# TAC_v1.net
KiCad netlist of a schematic drawn in Altium Designer
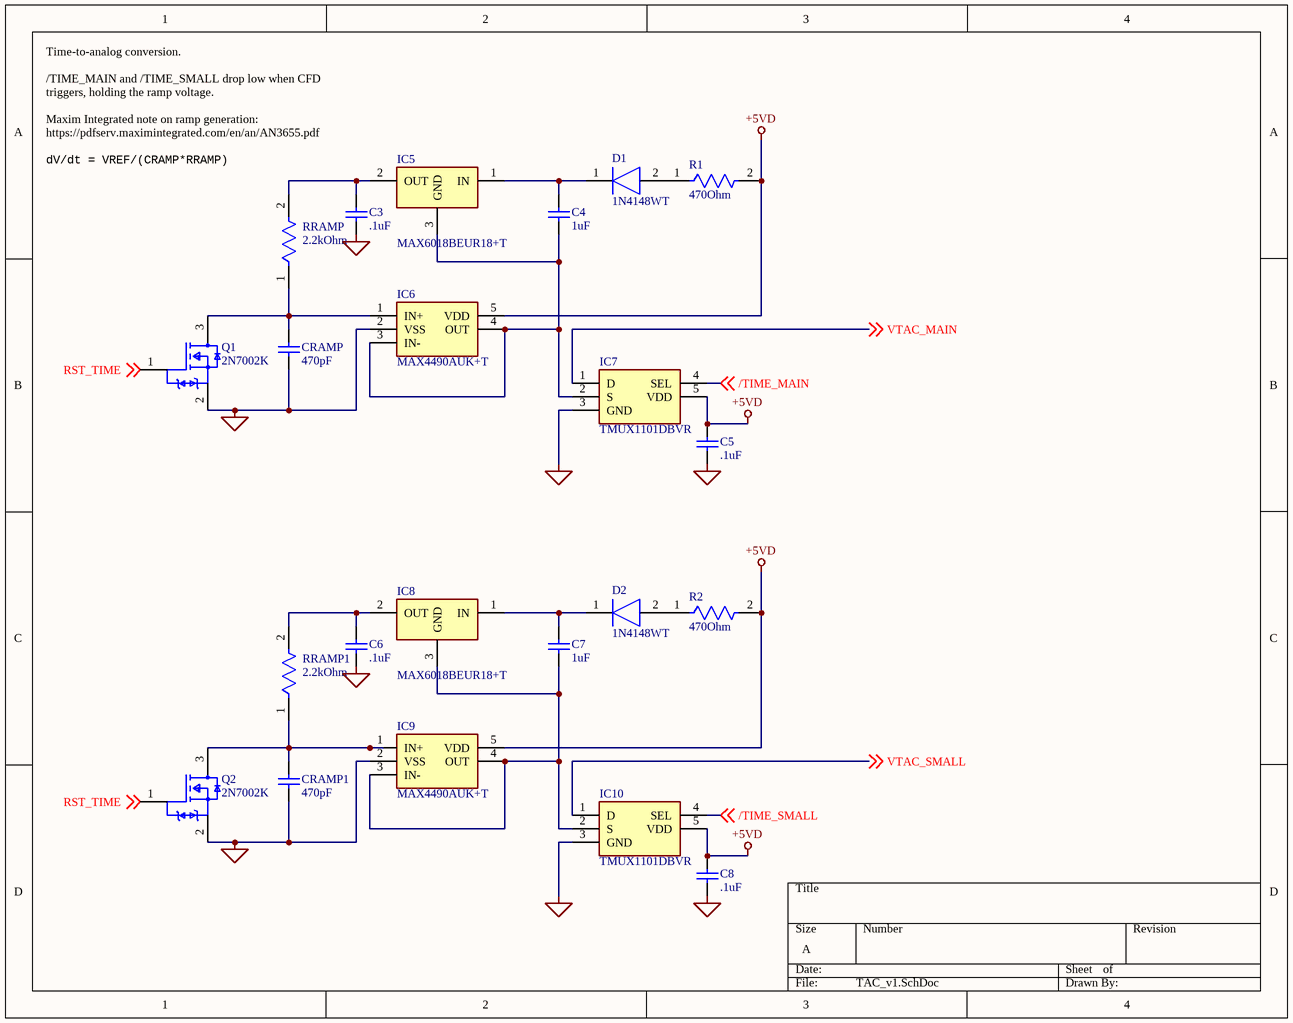
[diagram p0: TAC_v1.SchDoc]

(export (version "E")
  (design (tool "Eeschema 10.0.6"))
  (components
    (comp (ref "C3")
      (value ".1uF")
      (footprint "CAPC2013X140X45NL15T25")
      (description "0402")
      (fields (field (name "PART NUMBER") "GRM21BR71A106KE51L") (field (name "MANUFACTURER") "Murata"))
      (libsource (lib "Altium Content Vault") (part "CAP"))
    )
    (comp (ref "C4")
      (value "1uF")
      (footprint "CAPC2013X140X45NL15T25")
      (description "0402")
      (fields (field (name "PART NUMBER") "GRM21BR71A106KE51L") (field (name "MANUFACTURER") "Murata"))
      (libsource (lib "Altium Content Vault") (part "CAP"))
    )
    (comp (ref "C5")
      (value ".1uF")
      (footprint "CAPC2013X140X45NL15T25")
      (description "0402")
      (fields (field (name "PART NUMBER") "GRM21BR71A106KE51L") (field (name "MANUFACTURER") "Murata"))
      (libsource (lib "Altium Content Vault") (part "CAP"))
    )
    (comp (ref "C6")
      (value ".1uF")
      (footprint "CAPC2013X140X45NL15T25")
      (description "0402")
      (fields (field (name "PART NUMBER") "GRM21BR71A106KE51L") (field (name "MANUFACTURER") "Murata"))
      (libsource (lib "Altium Content Vault") (part "CAP"))
    )
    (comp (ref "C7")
      (value "1uF")
      (footprint "CAPC2013X140X45NL15T25")
      (description "0402")
      (fields (field (name "PART NUMBER") "GRM21BR71A106KE51L") (field (name "MANUFACTURER") "Murata"))
      (libsource (lib "Altium Content Vault") (part "CAP"))
    )
    (comp (ref "C8")
      (value ".1uF")
      (footprint "CAPC2013X140X45NL15T25")
      (description "0402")
      (fields (field (name "PART NUMBER") "GRM21BR71A106KE51L") (field (name "MANUFACTURER") "Murata"))
      (libsource (lib "Altium Content Vault") (part "CAP"))
    )
    (comp (ref "CRAMP")
      (value "470pF")
      (footprint "CAPC2013X140X45NL15T25")
      (description "0402")
      (fields (field (name "PART NUMBER") "GRM21BR71A106KE51L") (field (name "MANUFACTURER") "Murata"))
      (libsource (lib "Altium Content Vault") (part "CAP"))
    )
    (comp (ref "CRAMP1")
      (value "470pF")
      (footprint "CAPC2013X140X45NL15T25")
      (description "0402")
      (fields (field (name "PART NUMBER") "GRM21BR71A106KE51L") (field (name "MANUFACTURER") "Murata"))
      (libsource (lib "Altium Content Vault") (part "CAP"))
    )
    (comp (ref "D1")
      (value "1N4148WT")
      (footprint "SamacSys:SODFL1608X70N")
      (description "Diode")
      (libsource (lib "*") (part "1N4148WT"))
    )
    (comp (ref "D2")
      (value "1N4148WT")
      (footprint "SamacSys:SODFL1608X70N")
      (description "Diode")
      (libsource (lib "*") (part "1N4148WT"))
    )
    (comp (ref "IC5")
      (value "MAX6018BEUR18+T")
      (footprint "SamacSys:SOT95P237X112-3N")
      (description "Voltage References Precision, Micropower, 1.8V Supply, Low-Dropout, SOT23 Voltage Reference")
      (libsource (lib "SamacSys") (part "MAX6018BEUR18+T"))
    )
    (comp (ref "IC6")
      (value "MAX4490AUK+T")
      (footprint "SamacSys:SOT95P280X145-5N")
      (description "Integrated Circuit")
      (libsource (lib "SamacSys") (part "MAX4490AUK+T"))
    )
    (comp (ref "IC7")
      (value "TMUX1101DBVR")
      (footprint "SamacSys:SOT95P280X145-5N")
      (libsource (lib "*") (part "TMUX1101DBVR"))
    )
    (comp (ref "IC8")
      (value "MAX6018BEUR18+T")
      (footprint "SamacSys:SOT95P237X112-3N")
      (description "Voltage References Precision, Micropower, 1.8V Supply, Low-Dropout, SOT23 Voltage Reference")
      (libsource (lib "SamacSys") (part "MAX6018BEUR18+T"))
    )
    (comp (ref "IC9")
      (value "MAX4490AUK+T")
      (footprint "SamacSys:SOT95P280X145-5N")
      (description "Integrated Circuit")
      (libsource (lib "SamacSys") (part "MAX4490AUK+T"))
    )
    (comp (ref "IC10")
      (value "TMUX1101DBVR")
      (footprint "SamacSys:SOT95P280X145-5N")
      (libsource (lib "*") (part "TMUX1101DBVR"))
    )
    (comp (ref "Q1")
      (value "2N7002K")
      (footprint "FP-318-08-MFG")
      (description "MOSFET N-CH 60V 300MA SOT23")
      (fields
        (field (name "OCTOPART") "https://octopart.com/2n7002k-on+semiconductor-84408900")
        (field (name "MANUFACTURER") "ON Semiconductor")
      )
      (libsource (lib "Altium Content Vault") (part "40bafa8609a25cdbb0dab398ef4a0d9"))
    )
    (comp (ref "Q2")
      (value "2N7002K")
      (footprint "FP-318-08-MFG")
      (description "MOSFET N-CH 60V 300MA SOT23")
      (fields
        (field (name "OCTOPART") "https://octopart.com/2n7002k-on+semiconductor-84408900")
        (field (name "MANUFACTURER") "ON Semiconductor")
      )
      (libsource (lib "Altium Content Vault") (part "40bafa8609a25cdbb0dab398ef4a0d9"))
    )
    (comp (ref "R1")
      (value "470Ohm")
      (footprint "FP-CRCW0402-e3-IPC_C")
      (description "RES Thick Film, 0Ω, 0.063W, 0402")
      (fields (field (name "TOLERANCE") "5%"))
      (libsource (lib "Altium Content Vault") (part "1029c3af85768c4190bb7ad29bc67b5"))
    )
    (comp (ref "R2")
      (value "470Ohm")
      (footprint "FP-CRCW0402-e3-IPC_C")
      (description "RES Thick Film, 0Ω, 0.063W, 0402")
      (fields (field (name "TOLERANCE") "5%"))
      (libsource (lib "Altium Content Vault") (part "1029c3af85768c4190bb7ad29bc67b5"))
    )
    (comp (ref "RRAMP")
      (value "2.2kOhm")
      (footprint "FP-CRCW0603-e3-MFG")
      (description "RES Thick Film, 1MΩ, 1%, 0.1W, 100ppm/°C, 0603")
      (fields (field (name "TOLERANCE") "1%"))
      (libsource (lib "Altium Content Vault") (part "1029c3af85768c4190bb7ad29bc67b5"))
    )
    (comp (ref "RRAMP1")
      (value "2.2kOhm")
      (footprint "FP-CRCW0603-e3-MFG")
      (description "RES Thick Film, 1MΩ, 1%, 0.1W, 100ppm/°C, 0603")
      (fields (field (name "TOLERANCE") "1%"))
      (libsource (lib "Altium Content Vault") (part "1029c3af85768c4190bb7ad29bc67b5"))
    )
  )
  (nets
    (net (code "1") (name "+5VD") (class "Default")
      (node (ref "C5") (pin "2") (pinfunction "2_2") (pintype "passive"))
      (node (ref "C8") (pin "2") (pinfunction "2_2") (pintype "passive"))
      (node (ref "IC10") (pin "5") (pinfunction "VDD_5") (pintype "passive"))
      (node (ref "IC6") (pin "5") (pinfunction "VDD_5") (pintype "passive"))
      (node (ref "IC7") (pin "5") (pinfunction "VDD_5") (pintype "passive"))
      (node (ref "IC9") (pin "5") (pinfunction "VDD_5") (pintype "passive"))
      (node (ref "R1") (pin "2") (pinfunction "2_2") (pintype "passive"))
      (node (ref "R2") (pin "2") (pinfunction "2_2") (pintype "passive"))
    )
    (net (code "2") (name "GND") (class "Default")
      (node (ref "C3") (pin "1") (pinfunction "1_1") (pintype "passive"))
      (node (ref "C5") (pin "1") (pinfunction "1_1") (pintype "passive"))
      (node (ref "C6") (pin "1") (pinfunction "1_1") (pintype "passive"))
      (node (ref "C8") (pin "1") (pinfunction "1_1") (pintype "passive"))
      (node (ref "CRAMP") (pin "1") (pinfunction "1_1") (pintype "passive"))
      (node (ref "CRAMP1") (pin "1") (pinfunction "1_1") (pintype "passive"))
      (node (ref "IC10") (pin "3") (pinfunction "GND_3") (pintype "passive"))
      (node (ref "IC6") (pin "2") (pinfunction "VSS_2") (pintype "passive"))
      (node (ref "IC7") (pin "3") (pinfunction "GND_3") (pintype "passive"))
      (node (ref "IC9") (pin "2") (pinfunction "VSS_2") (pintype "passive"))
      (node (ref "Q1") (pin "2") (pinfunction "Source_2") (pintype "passive"))
      (node (ref "Q2") (pin "2") (pinfunction "Source_2") (pintype "passive"))
    )
    (net (code "3") (name "Net-(D1-A)") (class "Default")
      (node (ref "D1") (pin "2") (pinfunction "A_2") (pintype "passive"))
      (node (ref "R1") (pin "1") (pinfunction "1_1") (pintype "passive"))
    )
    (net (code "4") (name "Net-(D1-K)") (class "Default")
      (node (ref "C4") (pin "2") (pinfunction "2_2") (pintype "passive"))
      (node (ref "D1") (pin "1") (pinfunction "K_1") (pintype "passive"))
      (node (ref "IC5") (pin "1") (pinfunction "IN_1") (pintype "passive"))
    )
    (net (code "5") (name "Net-(D2-A)") (class "Default")
      (node (ref "D2") (pin "2") (pinfunction "A_2") (pintype "passive"))
      (node (ref "R2") (pin "1") (pinfunction "1_1") (pintype "passive"))
    )
    (net (code "6") (name "Net-(D2-K)") (class "Default")
      (node (ref "C7") (pin "2") (pinfunction "2_2") (pintype "passive"))
      (node (ref "D2") (pin "1") (pinfunction "K_1") (pintype "passive"))
      (node (ref "IC8") (pin "1") (pinfunction "IN_1") (pintype "passive"))
    )
    (net (code "7") (name "Net-(IC5-GND)") (class "Default")
      (node (ref "C4") (pin "1") (pinfunction "1_1") (pintype "passive"))
      (node (ref "IC5") (pin "3") (pinfunction "GND_3") (pintype "passive"))
      (node (ref "IC6") (pin "3") (pinfunction "IN-_3") (pintype "passive"))
      (node (ref "IC6") (pin "4") (pinfunction "OUT_4") (pintype "passive"))
      (node (ref "IC7") (pin "2") (pinfunction "S_2") (pintype "passive"))
    )
    (net (code "8") (name "Net-(IC5-OUT)") (class "Default")
      (node (ref "C3") (pin "2") (pinfunction "2_2") (pintype "passive"))
      (node (ref "IC5") (pin "2") (pinfunction "OUT_2") (pintype "passive"))
      (node (ref "RRAMP") (pin "2") (pinfunction "2_2") (pintype "passive"))
    )
    (net (code "9") (name "Net-(IC6-IN+)") (class "Default")
      (node (ref "CRAMP") (pin "2") (pinfunction "2_2") (pintype "passive"))
      (node (ref "IC6") (pin "1") (pinfunction "IN+_1") (pintype "passive"))
      (node (ref "Q1") (pin "3") (pinfunction "Drain_3") (pintype "passive"))
      (node (ref "RRAMP") (pin "1") (pinfunction "1_1") (pintype "passive"))
    )
    (net (code "10") (name "Net-(IC8-OUT)") (class "Default")
      (node (ref "C6") (pin "2") (pinfunction "2_2") (pintype "passive"))
      (node (ref "IC8") (pin "2") (pinfunction "OUT_2") (pintype "passive"))
      (node (ref "RRAMP1") (pin "2") (pinfunction "2_2") (pintype "passive"))
    )
    (net (code "11") (name "Net-(IC9-IN+)") (class "Default")
      (node (ref "CRAMP1") (pin "2") (pinfunction "2_2") (pintype "passive"))
      (node (ref "IC9") (pin "1") (pinfunction "IN+_1") (pintype "passive"))
      (node (ref "Q2") (pin "3") (pinfunction "Drain_3") (pintype "passive"))
      (node (ref "RRAMP1") (pin "1") (pinfunction "1_1") (pintype "passive"))
    )
    (net (code "12") (name "Net-(IC10-S)") (class "Default")
      (node (ref "C7") (pin "1") (pinfunction "1_1") (pintype "passive"))
      (node (ref "IC10") (pin "2") (pinfunction "S_2") (pintype "passive"))
      (node (ref "IC8") (pin "3") (pinfunction "GND_3") (pintype "passive"))
      (node (ref "IC9") (pin "3") (pinfunction "IN-_3") (pintype "passive"))
      (node (ref "IC9") (pin "4") (pinfunction "OUT_4") (pintype "passive"))
    )
    (net (code "13") (name "RST_TIME") (class "Default")
      (node (ref "Q1") (pin "1") (pinfunction "Gate_1") (pintype "passive"))
      (node (ref "Q2") (pin "1") (pinfunction "Gate_1") (pintype "passive"))
    )
    (net (code "14") (name "VTAC_MAIN") (class "Default")
      (node (ref "IC7") (pin "1") (pinfunction "D_1") (pintype "passive"))
    )
    (net (code "15") (name "VTAC_SMALL") (class "Default")
      (node (ref "IC10") (pin "1") (pinfunction "D_1") (pintype "passive"))
    )
    (net (code "16") (name "{slash}TIME_MAIN") (class "Default")
      (node (ref "IC7") (pin "4") (pinfunction "SEL_4") (pintype "passive"))
    )
    (net (code "17") (name "{slash}TIME_SMALL") (class "Default")
      (node (ref "IC10") (pin "4") (pinfunction "SEL_4") (pintype "passive"))
    )
  )
)
